# LCD.net
KiCad netlist of a schematic drawn in Altium Designer
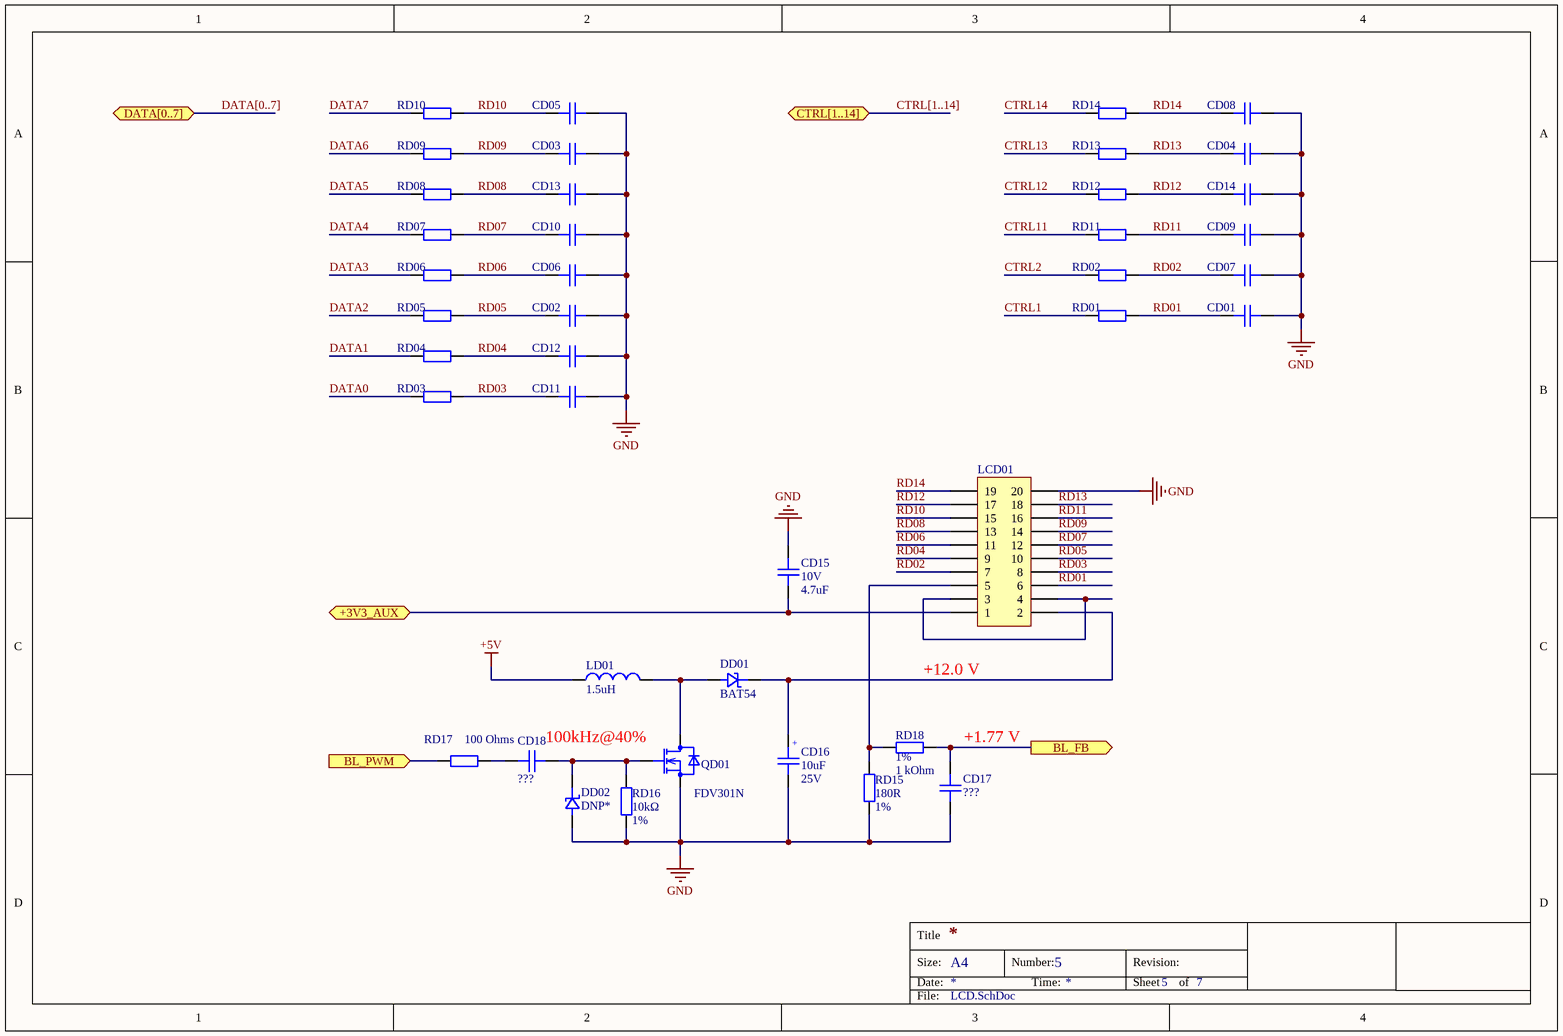
[diagram p0: LCD.SchDoc]

(export (version "E")
  (design (tool "Eeschema 10.0.6"))
  (components
    (comp (ref "CD01")
      (value "CAP CER 120PF 50V C0G/NP0 0603")
      (footprint "0603C")
      (description "120pF ±5% 50V Ceramic Capacitor C0G, NP0 0603 (1608 Metric)")
      (fields
        (field (name "MANUFACTURER") "KEMET")
        (field (name "MANUFACTURER PART NUMBER") "C0603C121J5GACTU")
      )
      (libsource (lib "capacitors_smd") (part "CAP CER 120PF 50V C0G/NP0 0603"))
    )
    (comp (ref "CD02")
      (value "CAP CER 120PF 50V C0G/NP0 0603")
      (footprint "0603C")
      (description "120pF ±5% 50V Ceramic Capacitor C0G, NP0 0603 (1608 Metric)")
      (fields
        (field (name "MANUFACTURER") "KEMET")
        (field (name "MANUFACTURER PART NUMBER") "C0603C121J5GACTU")
      )
      (libsource (lib "capacitors_smd") (part "CAP CER 120PF 50V C0G/NP0 0603"))
    )
    (comp (ref "CD03")
      (value "CAP CER 120PF 50V C0G/NP0 0603")
      (footprint "0603C")
      (description "120pF ±5% 50V Ceramic Capacitor C0G, NP0 0603 (1608 Metric)")
      (fields
        (field (name "MANUFACTURER") "KEMET")
        (field (name "MANUFACTURER PART NUMBER") "C0603C121J5GACTU")
      )
      (libsource (lib "capacitors_smd") (part "CAP CER 120PF 50V C0G/NP0 0603"))
    )
    (comp (ref "CD04")
      (value "CAP CER 120PF 50V C0G/NP0 0603")
      (footprint "0603C")
      (description "120pF ±5% 50V Ceramic Capacitor C0G, NP0 0603 (1608 Metric)")
      (fields
        (field (name "MANUFACTURER") "KEMET")
        (field (name "MANUFACTURER PART NUMBER") "C0603C121J5GACTU")
      )
      (libsource (lib "capacitors_smd") (part "CAP CER 120PF 50V C0G/NP0 0603"))
    )
    (comp (ref "CD05")
      (value "CAP CER 120PF 50V C0G/NP0 0603")
      (footprint "0603C")
      (description "120pF ±5% 50V Ceramic Capacitor C0G, NP0 0603 (1608 Metric)")
      (fields
        (field (name "MANUFACTURER") "KEMET")
        (field (name "MANUFACTURER PART NUMBER") "C0603C121J5GACTU")
      )
      (libsource (lib "capacitors_smd") (part "CAP CER 120PF 50V C0G/NP0 0603"))
    )
    (comp (ref "CD06")
      (value "CAP CER 120PF 50V C0G/NP0 0603")
      (footprint "0603C")
      (description "120pF ±5% 50V Ceramic Capacitor C0G, NP0 0603 (1608 Metric)")
      (fields
        (field (name "MANUFACTURER") "KEMET")
        (field (name "MANUFACTURER PART NUMBER") "C0603C121J5GACTU")
      )
      (libsource (lib "capacitors_smd") (part "CAP CER 120PF 50V C0G/NP0 0603"))
    )
    (comp (ref "CD07")
      (value "CAP CER 120PF 50V C0G/NP0 0603")
      (footprint "0603C")
      (description "120pF ±5% 50V Ceramic Capacitor C0G, NP0 0603 (1608 Metric)")
      (fields
        (field (name "MANUFACTURER") "KEMET")
        (field (name "MANUFACTURER PART NUMBER") "C0603C121J5GACTU")
      )
      (libsource (lib "capacitors_smd") (part "CAP CER 120PF 50V C0G/NP0 0603"))
    )
    (comp (ref "CD08")
      (value "CAP CER 120PF 50V C0G/NP0 0603")
      (footprint "0603C")
      (description "120pF ±5% 50V Ceramic Capacitor C0G, NP0 0603 (1608 Metric)")
      (fields
        (field (name "MANUFACTURER") "KEMET")
        (field (name "MANUFACTURER PART NUMBER") "C0603C121J5GACTU")
      )
      (libsource (lib "capacitors_smd") (part "CAP CER 120PF 50V C0G/NP0 0603"))
    )
    (comp (ref "CD09")
      (value "CAP CER 120PF 50V C0G/NP0 0603")
      (footprint "0603C")
      (description "120pF ±5% 50V Ceramic Capacitor C0G, NP0 0603 (1608 Metric)")
      (fields
        (field (name "MANUFACTURER") "KEMET")
        (field (name "MANUFACTURER PART NUMBER") "C0603C121J5GACTU")
      )
      (libsource (lib "capacitors_smd") (part "CAP CER 120PF 50V C0G/NP0 0603"))
    )
    (comp (ref "CD10")
      (value "CAP CER 120PF 50V C0G/NP0 0603")
      (footprint "0603C")
      (description "120pF ±5% 50V Ceramic Capacitor C0G, NP0 0603 (1608 Metric)")
      (fields
        (field (name "MANUFACTURER") "KEMET")
        (field (name "MANUFACTURER PART NUMBER") "C0603C121J5GACTU")
      )
      (libsource (lib "capacitors_smd") (part "CAP CER 120PF 50V C0G/NP0 0603"))
    )
    (comp (ref "CD11")
      (value "CAP CER 120PF 50V C0G/NP0 0603")
      (footprint "0603C")
      (description "120pF ±5% 50V Ceramic Capacitor C0G, NP0 0603 (1608 Metric)")
      (fields
        (field (name "MANUFACTURER") "KEMET")
        (field (name "MANUFACTURER PART NUMBER") "C0603C121J5GACTU")
      )
      (libsource (lib "capacitors_smd") (part "CAP CER 120PF 50V C0G/NP0 0603"))
    )
    (comp (ref "CD12")
      (value "CAP CER 120PF 50V C0G/NP0 0603")
      (footprint "0603C")
      (description "120pF ±5% 50V Ceramic Capacitor C0G, NP0 0603 (1608 Metric)")
      (fields
        (field (name "MANUFACTURER") "KEMET")
        (field (name "MANUFACTURER PART NUMBER") "C0603C121J5GACTU")
      )
      (libsource (lib "capacitors_smd") (part "CAP CER 120PF 50V C0G/NP0 0603"))
    )
    (comp (ref "CD13")
      (value "CAP CER 120PF 50V C0G/NP0 0603")
      (footprint "0603C")
      (description "120pF ±5% 50V Ceramic Capacitor C0G, NP0 0603 (1608 Metric)")
      (fields
        (field (name "MANUFACTURER") "KEMET")
        (field (name "MANUFACTURER PART NUMBER") "C0603C121J5GACTU")
      )
      (libsource (lib "capacitors_smd") (part "CAP CER 120PF 50V C0G/NP0 0603"))
    )
    (comp (ref "CD14")
      (value "CAP CER 120PF 50V C0G/NP0 0603")
      (footprint "0603C")
      (description "120pF ±5% 50V Ceramic Capacitor C0G, NP0 0603 (1608 Metric)")
      (fields
        (field (name "MANUFACTURER") "KEMET")
        (field (name "MANUFACTURER PART NUMBER") "C0603C121J5GACTU")
      )
      (libsource (lib "capacitors_smd") (part "CAP CER 120PF 50V C0G/NP0 0603"))
    )
    (comp (ref "CD15")
      (value "CAP CER 4.7UF 10V X5R 0603")
      (footprint "0603C")
      (description "4.7µF ±10% 10V Ceramic Capacitor X5R 0603 (1608 Metric)")
      (fields
        (field (name "MANUFACTURER") "Yageo")
        (field (name "MANUFACTURER PART NUMBER") "CC0603KRX5R6BB475")
        (field (name "VOLTAGE RATING") "10V")
        (field (name "CAPACITANCE") "4.7uF")
      )
      (libsource (lib "capacitors_smd") (part "CAP CER 4.7UF 10V X5R 0603"))
    )
    (comp (ref "CD16")
      (value "CAP ALUM 68 UF 20% 25 V SMD")
      (footprint "WCAP-ASLI_6.3x5.5")
      (description "68µF 25V Aluminum Electrolytic Capacitors Radial, Can - SMD  2000 Hrs @ 105°C")
      (fields
        (field (name "MANUFACTURER PART NUMBER") "865080443009")
        (field (name "MANUFACTURER") "Wurth Elektronik")
        (field (name "CAPACITANCE") "10uF")
        (field (name "RATED VOLTAGE") "25V")
      )
      (libsource (lib "capacitors_alum_electr_poly") (part "CAP ALUM 68 UF 20% 25 V SMD"))
    )
    (comp (ref "CD17")
      (value "CAP CER 0.1uF ±10% 50V X7R 0603")
      (footprint "CAPC1608X08N_0603")
      (description "Capacitor")
      (fields
        (field (name "MANUFACTURER") "KEMET")
        (field (name "MANUFACTURER PART NUMBER") "C0603C104M5RACTU")
        (field (name "CAPACITANCE") "???")
      )
      (libsource (lib "capacitors_smd") (part "CAP CER 0.1uF ±10% 50V X7R 0603"))
    )
    (comp (ref "CD18")
      (value "CAP CER 0.1uF ±10% 50V X7R 0603")
      (footprint "CAPC1608X08N_0603")
      (description "Capacitor")
      (fields
        (field (name "MANUFACTURER") "KEMET")
        (field (name "MANUFACTURER PART NUMBER") "C0603C104M5RACTU")
        (field (name "CAPACITANCE") "???")
      )
      (libsource (lib "capacitors_smd") (part "CAP CER 0.1uF ±10% 50V X7R 0603"))
    )
    (comp (ref "DD01")
      (value "BAT54")
      (footprint "SOT100P240X120-3N")
      (description "Schottky DiodeS")
      (libsource (lib "diodes_schottky") (part "BAT54"))
    )
    (comp (ref "DD02")
      (value "DNP*")
      (footprint "SOT100P240X120-3N")
      (description "Schottky DiodeS")
      (libsource (lib "diodes_schottky") (part "BAT54"))
    )
    (comp (ref "LCD01")
      (value "CONN HEADER SMD 20POS 2.54MM")
      (footprint "IDC_2X10 SMD")
      (description "Connector Header Surface Mount 20 position 0.100\" (2.54mm)")
      (fields
        (field (name "MANUFACTURER") "CNC Tech")
        (field (name "MANUFACTURER PART NUMBER") "3020-20-0300-00")
      )
      (libsource (lib "connectors_header") (part "CONN HEADER SMD 20POS 2.54MM"))
    )
    (comp (ref "LD01")
      (value "FIXED IND 1.5UH 6.2A 20 MOHM SMD")
      (description "1.5µH Shielded Molded Inductor 6.2A 20mOhm Max Nonstandard")
      (fields
        (field (name "MANUFACTURER") "Wurth Electronics")
        (field (name "MANUFACTURER PART NUMBER") "74438357015")
        (field (name "INDUCTANCE") "1.5uH")
      )
      (libsource (lib "inductors_smd") (part "FIXED IND 1.5UH 6.2A 20 MOHM SMD"))
    )
    (comp (ref "QD01")
      (value "FDV301N")
      (footprint "SOT-23/3")
      (description "N-Channel 25 V 220mA (Ta) 350mW (Ta) Surface Mount SOT-23-3")
      (libsource (lib "mosfets") (part "MOSFET FDV301N N-CH 25V 220MA SOT23"))
    )
    (comp (ref "RD01")
      (value "100 Ohms")
      (footprint "R_0603")
      (description "RES SMD 100 OHM 1% 1/8W 0603")
      (fields
        (field (name "DIGI-KEYPARTNUMBER") "MCT0603-100-CFCT-ND")
        (field (name "PARTNUMBER") "MCT06030C1000FP500")
      )
      (libsource (lib "resistors_smd") (part "RES_SMD_100_OHM_1%_1/8W_0603"))
    )
    (comp (ref "RD02")
      (value "100 Ohms")
      (footprint "R_0603")
      (description "RES SMD 100 OHM 1% 1/8W 0603")
      (fields
        (field (name "DIGI-KEYPARTNUMBER") "MCT0603-100-CFCT-ND")
        (field (name "PARTNUMBER") "MCT06030C1000FP500")
      )
      (libsource (lib "") (part "RES_SMD_100_OHM_1%_1/8W_0603_1"))
    )
    (comp (ref "RD03")
      (value "100 Ohms")
      (footprint "R_0603")
      (description "RES SMD 100 OHM 1% 1/8W 0603")
      (fields
        (field (name "DIGI-KEYPARTNUMBER") "MCT0603-100-CFCT-ND")
        (field (name "PARTNUMBER") "MCT06030C1000FP500")
      )
      (libsource (lib "resistors_smd") (part "RES_SMD_100_OHM_1%_1/8W_0603"))
    )
    (comp (ref "RD04")
      (value "100 Ohms")
      (footprint "R_0603")
      (description "RES SMD 100 OHM 1% 1/8W 0603")
      (fields
        (field (name "DIGI-KEYPARTNUMBER") "MCT0603-100-CFCT-ND")
        (field (name "PARTNUMBER") "MCT06030C1000FP500")
      )
      (libsource (lib "") (part "RES_SMD_100_OHM_1%_1/8W_0603_1"))
    )
    (comp (ref "RD05")
      (value "100 Ohms")
      (footprint "R_0603")
      (description "RES SMD 100 OHM 1% 1/8W 0603")
      (fields
        (field (name "DIGI-KEYPARTNUMBER") "MCT0603-100-CFCT-ND")
        (field (name "PARTNUMBER") "MCT06030C1000FP500")
      )
      (libsource (lib "resistors_smd") (part "RES_SMD_100_OHM_1%_1/8W_0603"))
    )
    (comp (ref "RD06")
      (value "100 Ohms")
      (footprint "R_0603")
      (description "RES SMD 100 OHM 1% 1/8W 0603")
      (fields
        (field (name "DIGI-KEYPARTNUMBER") "MCT0603-100-CFCT-ND")
        (field (name "PARTNUMBER") "MCT06030C1000FP500")
      )
      (libsource (lib "") (part "RES_SMD_100_OHM_1%_1/8W_0603_1"))
    )
    (comp (ref "RD07")
      (value "100 Ohms")
      (footprint "R_0603")
      (description "RES SMD 100 OHM 1% 1/8W 0603")
      (fields
        (field (name "DIGI-KEYPARTNUMBER") "MCT0603-100-CFCT-ND")
        (field (name "PARTNUMBER") "MCT06030C1000FP500")
      )
      (libsource (lib "resistors_smd") (part "RES_SMD_100_OHM_1%_1/8W_0603"))
    )
    (comp (ref "RD08")
      (value "100 Ohms")
      (footprint "R_0603")
      (description "RES SMD 100 OHM 1% 1/8W 0603")
      (fields
        (field (name "DIGI-KEYPARTNUMBER") "MCT0603-100-CFCT-ND")
        (field (name "PARTNUMBER") "MCT06030C1000FP500")
      )
      (libsource (lib "") (part "RES_SMD_100_OHM_1%_1/8W_0603_1"))
    )
    (comp (ref "RD09")
      (value "100 Ohms")
      (footprint "R_0603")
      (description "RES SMD 100 OHM 1% 1/8W 0603")
      (fields
        (field (name "DIGI-KEYPARTNUMBER") "MCT0603-100-CFCT-ND")
        (field (name "PARTNUMBER") "MCT06030C1000FP500")
      )
      (libsource (lib "resistors_smd") (part "RES_SMD_100_OHM_1%_1/8W_0603"))
    )
    (comp (ref "RD10")
      (value "100 Ohms")
      (footprint "R_0603")
      (description "RES SMD 100 OHM 1% 1/8W 0603")
      (fields
        (field (name "DIGI-KEYPARTNUMBER") "MCT0603-100-CFCT-ND")
        (field (name "PARTNUMBER") "MCT06030C1000FP500")
      )
      (libsource (lib "") (part "RES_SMD_100_OHM_1%_1/8W_0603_1"))
    )
    (comp (ref "RD11")
      (value "100 Ohms")
      (footprint "R_0603")
      (description "RES SMD 100 OHM 1% 1/8W 0603")
      (fields
        (field (name "DIGI-KEYPARTNUMBER") "MCT0603-100-CFCT-ND")
        (field (name "PARTNUMBER") "MCT06030C1000FP500")
      )
      (libsource (lib "resistors_smd") (part "RES_SMD_100_OHM_1%_1/8W_0603"))
    )
    (comp (ref "RD12")
      (value "100 Ohms")
      (footprint "R_0603")
      (description "RES SMD 100 OHM 1% 1/8W 0603")
      (fields
        (field (name "DIGI-KEYPARTNUMBER") "MCT0603-100-CFCT-ND")
        (field (name "PARTNUMBER") "MCT06030C1000FP500")
      )
      (libsource (lib "") (part "RES_SMD_100_OHM_1%_1/8W_0603_1"))
    )
    (comp (ref "RD13")
      (value "100 Ohms")
      (footprint "R_0603")
      (description "RES SMD 100 OHM 1% 1/8W 0603")
      (fields
        (field (name "DIGI-KEYPARTNUMBER") "MCT0603-100-CFCT-ND")
        (field (name "PARTNUMBER") "MCT06030C1000FP500")
      )
      (libsource (lib "resistors_smd") (part "RES_SMD_100_OHM_1%_1/8W_0603"))
    )
    (comp (ref "RD14")
      (value "100 Ohms")
      (footprint "R_0603")
      (description "RES SMD 100 OHM 1% 1/8W 0603")
      (fields
        (field (name "DIGI-KEYPARTNUMBER") "MCT0603-100-CFCT-ND")
        (field (name "PARTNUMBER") "MCT06030C1000FP500")
      )
      (libsource (lib "") (part "RES_SMD_100_OHM_1%_1/8W_0603_1"))
    )
    (comp (ref "RD15")
      (value "R 180Ω ±5% 0603 0.1W")
      (footprint "Resistor-0603")
      (description "Resistor")
      (fields
        (field (name "MANUFACTURER") "Stackpole Electronics")
        (field (name "MANUFACTURER PART NUMBER") "RMCF0603FT180R")
        (field (name "RESISTANCE") "180R")
        (field (name "TOLERANCE") "1%")
      )
      (libsource (lib "resistors_smd") (part "R 180Ω ±5% 0603 0.1W"))
    )
    (comp (ref "RD16")
      (value "RES SMD 10K OHM 1% 1/10W 0603")
      (footprint "R0603")
      (description "10 kOhms ±1% 0.1W, 1/10W Chip Resistor 0603 (1608 Metric)  Thick Film")
      (fields
        (field (name "MANUFACTURER") "Yageo")
        (field (name "MANUFACTURER PART NUMBER") "RC0603FR-0710KL")
        (field (name "RESISTANCE") "10kΩ")
        (field (name "TOLERANCE") "1%")
      )
      (libsource (lib "resistors_smd") (part "RES SMD 10K OHM 1% 1/10W 0603"))
    )
    (comp (ref "RD17")
      (value "100 Ohms")
      (footprint "R_0603")
      (description "RES SMD 100 OHM 1% 1/8W 0603")
      (fields
        (field (name "DIGI-KEYPARTNUMBER") "MCT0603-100-CFCT-ND")
        (field (name "PARTNUMBER") "MCT06030C1000FP500")
      )
      (libsource (lib "") (part "RES_SMD_100_OHM_1%_1/8W_0603_1"))
    )
    (comp (ref "RD18")
      (value "1 kOhms ±1% 0.1W, 1/10W Chip Resistor 0603 (1608 Metric) Moisture Resistant Thick Film")
      (footprint "R0603")
      (fields
        (field (name "MANUFACTURER") "Yageo")
        (field (name "MANUFACTURER PART NUMBER") "RC0603FR-071KL")
        (field (name "TOLERANCE") "1%")
        (field (name "RESISTANCE") "1 kOhm")
      )
      (libsource (lib "resistors_smd") (part "RES SMD 1K OHM 1% 1/10W 0603"))
    )
  )
  (nets
    (net (code "9") (name "+5V") (class "Default")
      (node (ref "LD01") (pin "1") (pinfunction "1_1") (pintype "passive"))
    )
    (net (code "10") (name "/+3V3_AUX") (class "Default")
      (node (ref "CD15") (pin "2") (pinfunction "2_2") (pintype "passive"))
      (node (ref "LCD01") (pin "1") (pinfunction "1_1") (pintype "passive"))
    )
    (net (code "11") (name "/BL_FB") (class "Default")
      (node (ref "CD17") (pin "1") (pinfunction "1_1") (pintype "passive"))
      (node (ref "RD18") (pin "2") (pinfunction "2_2") (pintype "passive"))
    )
    (net (code "12") (name "/BL_PWM") (class "Default")
      (node (ref "RD17") (pin "2") (pinfunction "2_2") (pintype "passive"))
    )
    (net (code "13") (name "/CTRL1") (class "Default")
      (node (ref "RD01") (pin "1") (pinfunction "1_1") (pintype "passive"))
    )
    (net (code "14") (name "/CTRL2") (class "Default")
      (node (ref "RD02") (pin "2") (pinfunction "2_2") (pintype "passive"))
    )
    (net (code "15") (name "/CTRL11") (class "Default")
      (node (ref "RD11") (pin "1") (pinfunction "1_1") (pintype "passive"))
    )
    (net (code "16") (name "/CTRL12") (class "Default")
      (node (ref "RD12") (pin "2") (pinfunction "2_2") (pintype "passive"))
    )
    (net (code "17") (name "/CTRL13") (class "Default")
      (node (ref "RD13") (pin "1") (pinfunction "1_1") (pintype "passive"))
    )
    (net (code "18") (name "/CTRL14") (class "Default")
      (node (ref "RD14") (pin "2") (pinfunction "2_2") (pintype "passive"))
    )
    (net (code "20") (name "/DATA0") (class "Default")
      (node (ref "RD03") (pin "1") (pinfunction "1_1") (pintype "passive"))
    )
    (net (code "21") (name "/DATA1") (class "Default")
      (node (ref "RD04") (pin "2") (pinfunction "2_2") (pintype "passive"))
    )
    (net (code "22") (name "/DATA2") (class "Default")
      (node (ref "RD05") (pin "1") (pinfunction "1_1") (pintype "passive"))
    )
    (net (code "23") (name "/DATA3") (class "Default")
      (node (ref "RD06") (pin "2") (pinfunction "2_2") (pintype "passive"))
    )
    (net (code "24") (name "/DATA4") (class "Default")
      (node (ref "RD07") (pin "1") (pinfunction "1_1") (pintype "passive"))
    )
    (net (code "25") (name "/DATA5") (class "Default")
      (node (ref "RD08") (pin "2") (pinfunction "2_2") (pintype "passive"))
    )
    (net (code "26") (name "/DATA6") (class "Default")
      (node (ref "RD09") (pin "1") (pinfunction "1_1") (pintype "passive"))
    )
    (net (code "27") (name "/DATA7") (class "Default")
      (node (ref "RD10") (pin "2") (pinfunction "2_2") (pintype "passive"))
    )
    (net (code "29") (name "/RD01") (class "Default")
      (node (ref "CD01") (pin "1") (pinfunction "1_1") (pintype "passive"))
      (node (ref "LCD01") (pin "6") (pinfunction "6_6") (pintype "passive"))
      (node (ref "RD01") (pin "2") (pinfunction "2_2") (pintype "passive"))
    )
    (net (code "30") (name "/RD02") (class "Default")
      (node (ref "CD07") (pin "1") (pinfunction "1_1") (pintype "passive"))
      (node (ref "LCD01") (pin "7") (pinfunction "7_7") (pintype "passive"))
      (node (ref "RD02") (pin "1") (pinfunction "1_1") (pintype "passive"))
    )
    (net (code "31") (name "/RD03") (class "Default")
      (node (ref "CD11") (pin "1") (pinfunction "1_1") (pintype "passive"))
      (node (ref "LCD01") (pin "8") (pinfunction "8_8") (pintype "passive"))
      (node (ref "RD03") (pin "2") (pinfunction "2_2") (pintype "passive"))
    )
    (net (code "32") (name "/RD04") (class "Default")
      (node (ref "CD12") (pin "1") (pinfunction "1_1") (pintype "passive"))
      (node (ref "LCD01") (pin "9") (pinfunction "9_9") (pintype "passive"))
      (node (ref "RD04") (pin "1") (pinfunction "1_1") (pintype "passive"))
    )
    (net (code "33") (name "/RD05") (class "Default")
      (node (ref "CD02") (pin "1") (pinfunction "1_1") (pintype "passive"))
      (node (ref "LCD01") (pin "10") (pinfunction "10_10") (pintype "passive"))
      (node (ref "RD05") (pin "2") (pinfunction "2_2") (pintype "passive"))
    )
    (net (code "34") (name "/RD06") (class "Default")
      (node (ref "CD06") (pin "1") (pinfunction "1_1") (pintype "passive"))
      (node (ref "LCD01") (pin "11") (pinfunction "11_11") (pintype "passive"))
      (node (ref "RD06") (pin "1") (pinfunction "1_1") (pintype "passive"))
    )
    (net (code "35") (name "/RD07") (class "Default")
      (node (ref "CD10") (pin "1") (pinfunction "1_1") (pintype "passive"))
      (node (ref "LCD01") (pin "12") (pinfunction "12_12") (pintype "passive"))
      (node (ref "RD07") (pin "2") (pinfunction "2_2") (pintype "passive"))
    )
    (net (code "36") (name "/RD08") (class "Default")
      (node (ref "CD13") (pin "1") (pinfunction "1_1") (pintype "passive"))
      (node (ref "LCD01") (pin "13") (pinfunction "13_13") (pintype "passive"))
      (node (ref "RD08") (pin "1") (pinfunction "1_1") (pintype "passive"))
    )
    (net (code "37") (name "/RD09") (class "Default")
      (node (ref "CD03") (pin "1") (pinfunction "1_1") (pintype "passive"))
      (node (ref "LCD01") (pin "14") (pinfunction "14_14") (pintype "passive"))
      (node (ref "RD09") (pin "2") (pinfunction "2_2") (pintype "passive"))
    )
    (net (code "38") (name "/RD10") (class "Default")
      (node (ref "CD05") (pin "1") (pinfunction "1_1") (pintype "passive"))
      (node (ref "LCD01") (pin "15") (pinfunction "15_15") (pintype "passive"))
      (node (ref "RD10") (pin "1") (pinfunction "1_1") (pintype "passive"))
    )
    (net (code "39") (name "/RD11") (class "Default")
      (node (ref "CD09") (pin "1") (pinfunction "1_1") (pintype "passive"))
      (node (ref "LCD01") (pin "16") (pinfunction "16_16") (pintype "passive"))
      (node (ref "RD11") (pin "2") (pinfunction "2_2") (pintype "passive"))
    )
    (net (code "40") (name "/RD12") (class "Default")
      (node (ref "CD14") (pin "1") (pinfunction "1_1") (pintype "passive"))
      (node (ref "LCD01") (pin "17") (pinfunction "17_17") (pintype "passive"))
      (node (ref "RD12") (pin "1") (pinfunction "1_1") (pintype "passive"))
    )
    (net (code "41") (name "/RD13") (class "Default")
      (node (ref "CD04") (pin "1") (pinfunction "1_1") (pintype "passive"))
      (node (ref "LCD01") (pin "18") (pinfunction "18_18") (pintype "passive"))
      (node (ref "RD13") (pin "2") (pinfunction "2_2") (pintype "passive"))
    )
    (net (code "42") (name "/RD14") (class "Default")
      (node (ref "CD08") (pin "1") (pinfunction "1_1") (pintype "passive"))
      (node (ref "LCD01") (pin "19") (pinfunction "19_19") (pintype "passive"))
      (node (ref "RD14") (pin "1") (pinfunction "1_1") (pintype "passive"))
    )
    (net (code "43") (name "GND") (class "Default")
      (node (ref "CD01") (pin "2") (pinfunction "2_2") (pintype "passive"))
      (node (ref "CD02") (pin "2") (pinfunction "2_2") (pintype "passive"))
      (node (ref "CD03") (pin "2") (pinfunction "2_2") (pintype "passive"))
      (node (ref "CD04") (pin "2") (pinfunction "2_2") (pintype "passive"))
      (node (ref "CD05") (pin "2") (pinfunction "2_2") (pintype "passive"))
      (node (ref "CD06") (pin "2") (pinfunction "2_2") (pintype "passive"))
      (node (ref "CD07") (pin "2") (pinfunction "2_2") (pintype "passive"))
      (node (ref "CD08") (pin "2") (pinfunction "2_2") (pintype "passive"))
      (node (ref "CD09") (pin "2") (pinfunction "2_2") (pintype "passive"))
      (node (ref "CD10") (pin "2") (pinfunction "2_2") (pintype "passive"))
      (node (ref "CD11") (pin "2") (pinfunction "2_2") (pintype "passive"))
      (node (ref "CD12") (pin "2") (pinfunction "2_2") (pintype "passive"))
      (node (ref "CD13") (pin "2") (pinfunction "2_2") (pintype "passive"))
      (node (ref "CD14") (pin "2") (pinfunction "2_2") (pintype "passive"))
      (node (ref "CD15") (pin "1") (pinfunction "1_1") (pintype "passive"))
      (node (ref "CD16") (pin "2") (pinfunction "2_2") (pintype "passive"))
      (node (ref "CD17") (pin "2") (pinfunction "2_2") (pintype "passive"))
      (node (ref "DD02") (pin "1") (pinfunction "1_1") (pintype "passive"))
      (node (ref "LCD01") (pin "20") (pinfunction "20_20") (pintype "passive"))
      (node (ref "QD01") (pin "2") (pinfunction "S_2") (pintype "passive"))
      (node (ref "RD15") (pin "1") (pinfunction "1_1") (pintype "passive"))
      (node (ref "RD16") (pin "1") (pinfunction "1_1") (pintype "passive"))
    )
    (net (code "44") (name "Net-(CD16-Pad1)") (class "Default")
      (node (ref "CD16") (pin "1") (pinfunction "1_1") (pintype "passive"))
      (node (ref "DD01") (pin "3") (pinfunction "3_3") (pintype "passive"))
      (node (ref "LCD01") (pin "2") (pinfunction "2_2") (pintype "passive"))
    )
    (net (code "45") (name "Net-(CD18-Pad2)") (class "Default")
      (node (ref "CD18") (pin "2") (pinfunction "2_2") (pintype "passive"))
      (node (ref "RD17") (pin "1") (pinfunction "1_1") (pintype "passive"))
    )
    (net (code "46") (name "Net-(LCD01-Pad3)") (class "Default")
      (node (ref "LCD01") (pin "3") (pinfunction "3_3") (pintype "passive"))
      (node (ref "LCD01") (pin "4") (pinfunction "4_4") (pintype "passive"))
    )
    (net (code "47") (name "Net-(LCD01-Pad5)") (class "Default")
      (node (ref "LCD01") (pin "5") (pinfunction "5_5") (pintype "passive"))
      (node (ref "RD15") (pin "2") (pinfunction "2_2") (pintype "passive"))
      (node (ref "RD18") (pin "1") (pinfunction "1_1") (pintype "passive"))
    )
    (net (code "48") (name "Net-(QD01-D)") (class "Default")
      (node (ref "DD01") (pin "1") (pinfunction "1_1") (pintype "passive"))
      (node (ref "LD01") (pin "2") (pinfunction "2_2") (pintype "passive"))
      (node (ref "QD01") (pin "3") (pinfunction "D_3") (pintype "passive"))
    )
    (net (code "49") (name "Net-(QD01-G)") (class "Default")
      (node (ref "CD18") (pin "1") (pinfunction "1_1") (pintype "passive"))
      (node (ref "DD02") (pin "3") (pinfunction "3_3") (pintype "passive"))
      (node (ref "QD01") (pin "1") (pinfunction "G_1") (pintype "passive"))
      (node (ref "RD16") (pin "2") (pinfunction "2_2") (pintype "passive"))
    )
  )
)
